# 2002A.net
KiCad netlist of a schematic drawn in Altium Designer
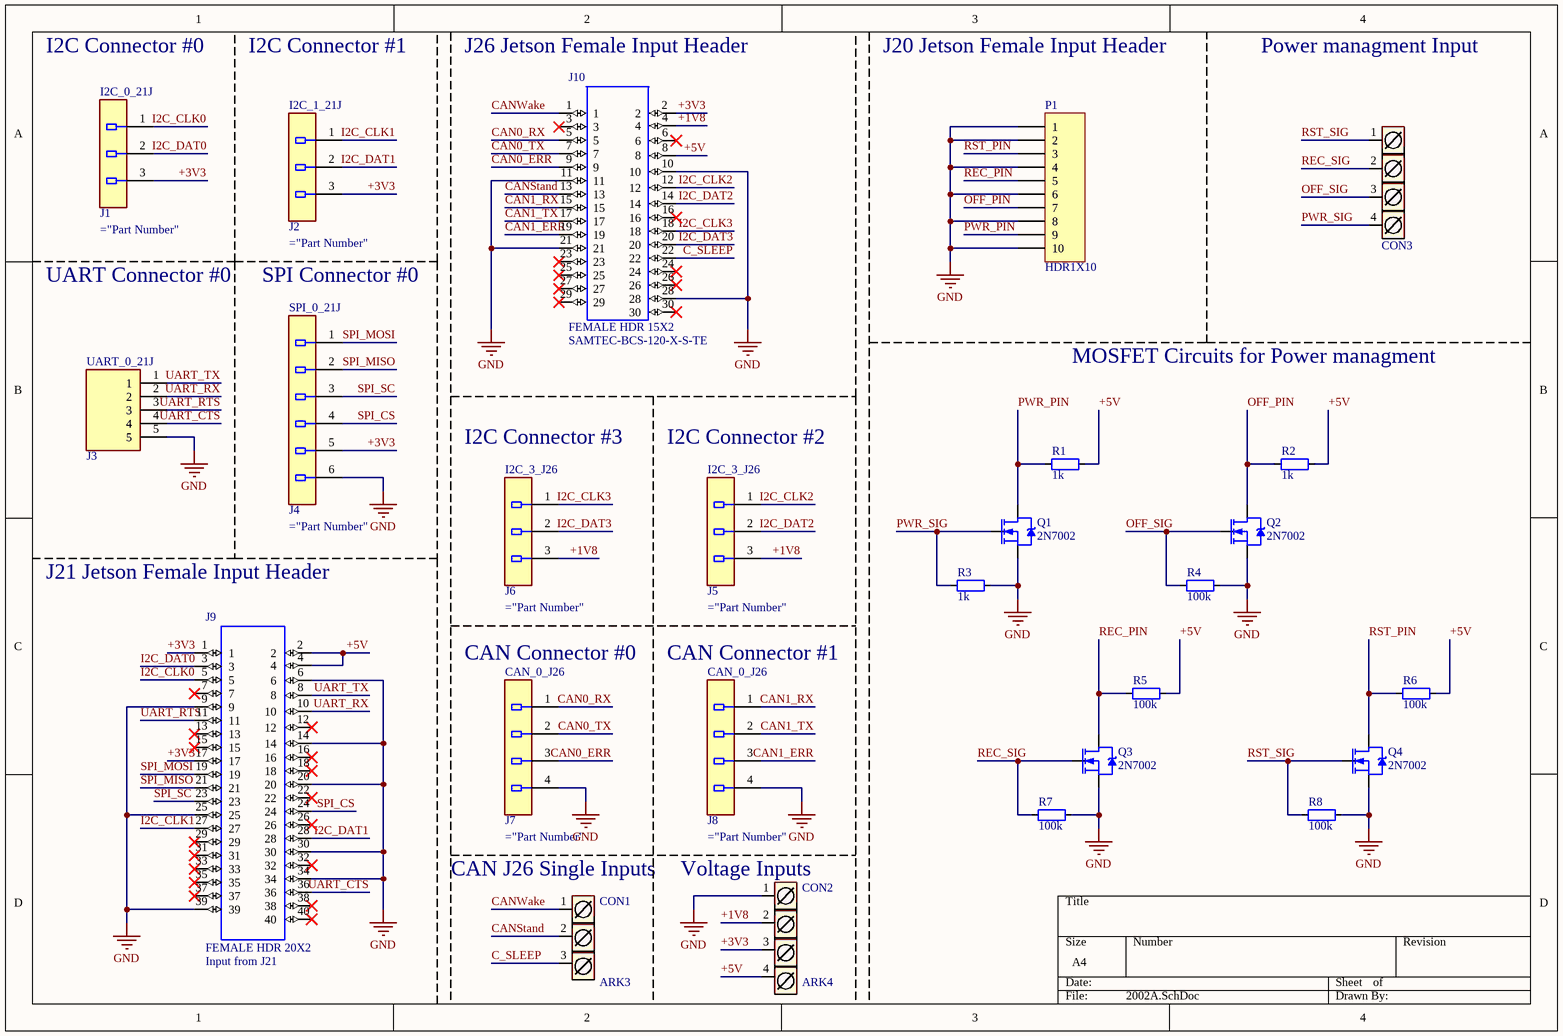
[diagram p0: 2002A.SchDoc]

(export (version "E")
  (design (tool "Eeschema 10.0.6"))
  (components
    (comp (ref "CON1")
      (value "ARK3")
      (footprint "ARK3")
      (description "Złącze śrubowe 3 piny")
      (libsource (lib "KNR_Kurs") (part "ARK3"))
    )
    (comp (ref "CON2")
      (value "ARK4")
      (footprint "ARK4")
      (description "Złącze śrubowe 4 piny")
      (libsource (lib "KNR_Kurs") (part "ARK4"))
    )
    (comp (ref "CON3")
      (value "ARK4")
      (footprint "ARK4")
      (description "Złącze śrubowe 4 piny")
      (libsource (lib "biblioteka_schematic") (part "ARK4"))
    )
    (comp (ref "J1")
      (value "I2C_0_21J")
      (footprint "Molex_22-05-7035_MFG")
      (description "I2C0")
      (libsource (lib "Conn_Molex_22-05-7035_eec") (part "22-05-7035"))
    )
    (comp (ref "J2")
      (value "I2C_1_21J")
      (footprint "Molex_22-05-7035_MFG")
      (description "I2C1")
      (libsource (lib "Conn_Molex_22-05-7035_eec") (part "22-05-7035"))
    )
    (comp (ref "J3")
      (value "UART_0_21J")
      (footprint "SamacSys:0022057055")
      (description "Connector")
      (fields (field (name "MANUFACTURER_PART_NUMBER") "0022057055"))
      (libsource (lib "MolexSpox5Ver") (part "0022057055"))
    )
    (comp (ref "J4")
      (value "SPI_0_21J")
      (footprint "Molex_22-05-7065_0")
      (libsource (lib "Conn_Molex_22-05-7065_eec") (part "22-05-7065"))
    )
    (comp (ref "J5")
      (value "I2C_3_J26")
      (footprint "Molex_22-05-7035_MFG")
      (description "I2C2")
      (libsource (lib "Conn_Molex_22-05-7035_eec") (part "22-05-7035"))
    )
    (comp (ref "J6")
      (value "I2C_3_J26")
      (footprint "Molex_22-05-7035_MFG")
      (description "I2C3")
      (libsource (lib "Conn_Molex_22-05-7035_eec") (part "22-05-7035"))
    )
    (comp (ref "J7")
      (value "CAN_0_J26")
      (footprint "Molex_22-05-7045_0")
      (description "CAN0")
      (libsource (lib "Conn_Molex_22-05-7045_eec") (part "22-05-7045"))
    )
    (comp (ref "J8")
      (value "CAN_0_J26")
      (footprint "Molex_22-05-7045_0")
      (description "CAN1")
      (libsource (lib "Conn_Molex_22-05-7045_eec") (part "22-05-7045"))
    )
    (comp (ref "J9")
      (value "Input from J21")
      (footprint "SSW-120-XX-X-D")
      (description "20 Position Receptacle Connector Through Hole")
      (fields (field (name "MP") "BCS-120-S-S-TE") (field (name "MF") "Samtec"))
      (libsource (lib "fHDR20x2") (part "SAMTEC-BCS-120-X-S-TE"))
    )
    (comp (ref "J10")
      (value "SAMTEC-BCS-120-X-S-TE")
      (footprint "SSW-115-XX-XXX-D")
      (description "20 Position Receptacle Connector Through Hole")
      (fields (field (name "MP") "BCS-120-S-S-TE") (field (name "MF") "Samtec"))
      (libsource (lib "fHDR15x2") (part "SAMTEC-BCS-120-X-S-TE"))
    )
    (comp (ref "P1")
      (value "HDR1X10")
      (footprint "biblioteka_pcb:HDR1X10")
      (description "Header, 10-Pin")
      (fields (field (name "PUBLISHER") "Altium Limited"))
      (libsource (lib "biblioteka_schematic") (part "HDR1X10"))
    )
    (comp (ref "Q1") (value "2N7002") (footprint "SOT23") (libsource (lib "KNR_Kurs") (part "2N7002")))
    (comp (ref "Q2") (value "2N7002") (footprint "SOT23") (libsource (lib "KNR_Kurs") (part "2N7002")))
    (comp (ref "Q3") (value "2N7002") (footprint "SOT23") (libsource (lib "KNR_Kurs") (part "2N7002")))
    (comp (ref "Q4") (value "2N7002") (footprint "SOT23") (libsource (lib "KNR_Kurs") (part "2N7002")))
    (comp (ref "R1")
      (value "1k")
      (footprint "0603")
      (description "Resistior")
      (libsource (lib "biblioteka_schematic") (part "RES"))
    )
    (comp (ref "R2")
      (value "1k")
      (footprint "0603")
      (description "Resistior")
      (libsource (lib "biblioteka_schematic") (part "RES"))
    )
    (comp (ref "R3")
      (value "1k")
      (footprint "0603")
      (description "Resistior")
      (libsource (lib "biblioteka_schematic") (part "RES"))
    )
    (comp (ref "R4")
      (value "100k")
      (footprint "0603")
      (description "Resistior")
      (libsource (lib "biblioteka_schematic") (part "RES"))
    )
    (comp (ref "R5")
      (value "100k")
      (footprint "0603")
      (description "Resistior")
      (libsource (lib "biblioteka_schematic") (part "RES"))
    )
    (comp (ref "R6")
      (value "100k")
      (footprint "0603")
      (description "Resistior")
      (libsource (lib "biblioteka_schematic") (part "RES"))
    )
    (comp (ref "R7")
      (value "100k")
      (footprint "0603")
      (description "Resistior")
      (libsource (lib "biblioteka_schematic") (part "RES"))
    )
    (comp (ref "R8")
      (value "100k")
      (footprint "0603")
      (description "Resistior")
      (libsource (lib "biblioteka_schematic") (part "RES"))
    )
  )
  (nets
    (net (code "1") (name "/+1V8") (class "Default")
      (node (ref "CON2") (pin "2") (pinfunction "2_2") (pintype "passive"))
      (node (ref "J10") (pin "4") (pinfunction "4_4") (pintype "bidirectional"))
      (node (ref "J5") (pin "3") (pinfunction "3_3") (pintype "passive"))
      (node (ref "J6") (pin "3") (pinfunction "3_3") (pintype "passive"))
    )
    (net (code "2") (name "/+3V3") (class "Default")
      (node (ref "CON2") (pin "3") (pinfunction "3_3") (pintype "passive"))
      (node (ref "J1") (pin "3") (pinfunction "3_3") (pintype "passive"))
      (node (ref "J10") (pin "2") (pinfunction "2_2") (pintype "bidirectional"))
      (node (ref "J2") (pin "3") (pinfunction "3_3") (pintype "passive"))
      (node (ref "J4") (pin "5") (pinfunction "5_5") (pintype "passive"))
      (node (ref "J9") (pin "1") (pinfunction "1_1") (pintype "bidirectional"))
      (node (ref "J9") (pin "17") (pinfunction "17_17") (pintype "bidirectional"))
    )
    (net (code "3") (name "/+5V") (class "Default")
      (node (ref "CON2") (pin "4") (pinfunction "4_4") (pintype "passive"))
      (node (ref "J10") (pin "8") (pinfunction "8_8") (pintype "bidirectional"))
      (node (ref "J9") (pin "2") (pinfunction "2_2") (pintype "bidirectional"))
      (node (ref "J9") (pin "4") (pinfunction "4_4") (pintype "bidirectional"))
      (node (ref "R1") (pin "2") (pinfunction "2_2") (pintype "passive"))
      (node (ref "R2") (pin "2") (pinfunction "2_2") (pintype "passive"))
      (node (ref "R5") (pin "2") (pinfunction "2_2") (pintype "passive"))
      (node (ref "R6") (pin "2") (pinfunction "2_2") (pintype "passive"))
    )
    (net (code "4") (name "/CAN0_ERR") (class "Default")
      (node (ref "J10") (pin "9") (pinfunction "9_9") (pintype "bidirectional"))
      (node (ref "J7") (pin "3") (pinfunction "3_3") (pintype "passive"))
    )
    (net (code "5") (name "/CAN0_RX") (class "Default")
      (node (ref "J10") (pin "5") (pinfunction "5_5") (pintype "bidirectional"))
      (node (ref "J7") (pin "1") (pinfunction "1_1") (pintype "passive"))
    )
    (net (code "6") (name "/CAN0_TX") (class "Default")
      (node (ref "J10") (pin "7") (pinfunction "7_7") (pintype "bidirectional"))
      (node (ref "J7") (pin "2") (pinfunction "2_2") (pintype "passive"))
    )
    (net (code "7") (name "/CAN1_ERR") (class "Default")
      (node (ref "J10") (pin "19") (pinfunction "19_19") (pintype "bidirectional"))
      (node (ref "J8") (pin "3") (pinfunction "3_3") (pintype "passive"))
    )
    (net (code "8") (name "/CAN1_RX") (class "Default")
      (node (ref "J10") (pin "15") (pinfunction "15_15") (pintype "bidirectional"))
      (node (ref "J8") (pin "1") (pinfunction "1_1") (pintype "passive"))
    )
    (net (code "9") (name "/CAN1_TX") (class "Default")
      (node (ref "J10") (pin "17") (pinfunction "17_17") (pintype "bidirectional"))
      (node (ref "J8") (pin "2") (pinfunction "2_2") (pintype "passive"))
    )
    (net (code "10") (name "/CANStand") (class "Default")
      (node (ref "CON1") (pin "2") (pinfunction "2_2") (pintype "passive"))
      (node (ref "J10") (pin "13") (pinfunction "13_13") (pintype "bidirectional"))
    )
    (net (code "11") (name "/CANWake") (class "Default")
      (node (ref "CON1") (pin "1") (pinfunction "1_1") (pintype "passive"))
      (node (ref "J10") (pin "1") (pinfunction "1_1") (pintype "bidirectional"))
    )
    (net (code "12") (name "/C_SLEEP") (class "Default")
      (node (ref "CON1") (pin "3") (pinfunction "3_3") (pintype "passive"))
      (node (ref "J10") (pin "22") (pinfunction "22_22") (pintype "bidirectional"))
    )
    (net (code "13") (name "/I2C_CLK0") (class "Default")
      (node (ref "J1") (pin "1") (pinfunction "1_1") (pintype "passive"))
      (node (ref "J9") (pin "5") (pinfunction "5_5") (pintype "bidirectional"))
    )
    (net (code "14") (name "/I2C_CLK1") (class "Default")
      (node (ref "J2") (pin "1") (pinfunction "1_1") (pintype "passive"))
      (node (ref "J9") (pin "27") (pinfunction "27_27") (pintype "bidirectional"))
    )
    (net (code "15") (name "/I2C_CLK2") (class "Default")
      (node (ref "J10") (pin "12") (pinfunction "12_12") (pintype "bidirectional"))
      (node (ref "J5") (pin "1") (pinfunction "1_1") (pintype "passive"))
    )
    (net (code "16") (name "/I2C_CLK3") (class "Default")
      (node (ref "J10") (pin "18") (pinfunction "18_18") (pintype "bidirectional"))
      (node (ref "J6") (pin "1") (pinfunction "1_1") (pintype "passive"))
    )
    (net (code "17") (name "/I2C_DAT0") (class "Default")
      (node (ref "J1") (pin "2") (pinfunction "2_2") (pintype "passive"))
      (node (ref "J9") (pin "3") (pinfunction "3_3") (pintype "bidirectional"))
    )
    (net (code "18") (name "/I2C_DAT1") (class "Default")
      (node (ref "J2") (pin "2") (pinfunction "2_2") (pintype "passive"))
      (node (ref "J9") (pin "28") (pinfunction "28_28") (pintype "bidirectional"))
    )
    (net (code "19") (name "/I2C_DAT2") (class "Default")
      (node (ref "J10") (pin "14") (pinfunction "14_14") (pintype "bidirectional"))
      (node (ref "J5") (pin "2") (pinfunction "2_2") (pintype "passive"))
    )
    (net (code "20") (name "/I2C_DAT3") (class "Default")
      (node (ref "J10") (pin "20") (pinfunction "20_20") (pintype "bidirectional"))
      (node (ref "J6") (pin "2") (pinfunction "2_2") (pintype "passive"))
    )
    (net (code "21") (name "/OFF_PIN") (class "Default")
      (node (ref "P1") (pin "7") (pinfunction "7_7") (pintype "passive"))
      (node (ref "Q2") (pin "3") (pinfunction "D_3") (pintype "passive"))
      (node (ref "R2") (pin "1") (pinfunction "1_1") (pintype "passive"))
    )
    (net (code "22") (name "/OFF_SIG") (class "Default")
      (node (ref "CON3") (pin "3") (pinfunction "3_3") (pintype "passive"))
      (node (ref "Q2") (pin "1") (pinfunction "G_1") (pintype "passive"))
      (node (ref "R4") (pin "1") (pinfunction "1_1") (pintype "passive"))
    )
    (net (code "23") (name "/PWR_PIN") (class "Default")
      (node (ref "P1") (pin "9") (pinfunction "9_9") (pintype "passive"))
      (node (ref "Q1") (pin "3") (pinfunction "D_3") (pintype "passive"))
      (node (ref "R1") (pin "1") (pinfunction "1_1") (pintype "passive"))
    )
    (net (code "24") (name "/PWR_SIG") (class "Default")
      (node (ref "CON3") (pin "4") (pinfunction "4_4") (pintype "passive"))
      (node (ref "Q1") (pin "1") (pinfunction "G_1") (pintype "passive"))
      (node (ref "R3") (pin "1") (pinfunction "1_1") (pintype "passive"))
    )
    (net (code "25") (name "/REC_PIN") (class "Default")
      (node (ref "P1") (pin "5") (pinfunction "5_5") (pintype "passive"))
      (node (ref "Q3") (pin "3") (pinfunction "D_3") (pintype "passive"))
      (node (ref "R5") (pin "1") (pinfunction "1_1") (pintype "passive"))
    )
    (net (code "26") (name "/REC_SIG") (class "Default")
      (node (ref "CON3") (pin "2") (pinfunction "2_2") (pintype "passive"))
      (node (ref "Q3") (pin "1") (pinfunction "G_1") (pintype "passive"))
      (node (ref "R7") (pin "1") (pinfunction "1_1") (pintype "passive"))
    )
    (net (code "27") (name "/RST_PIN") (class "Default")
      (node (ref "P1") (pin "3") (pinfunction "3_3") (pintype "passive"))
      (node (ref "Q4") (pin "3") (pinfunction "D_3") (pintype "passive"))
      (node (ref "R6") (pin "1") (pinfunction "1_1") (pintype "passive"))
    )
    (net (code "28") (name "/RST_SIG") (class "Default")
      (node (ref "CON3") (pin "1") (pinfunction "1_1") (pintype "passive"))
      (node (ref "Q4") (pin "1") (pinfunction "G_1") (pintype "passive"))
      (node (ref "R8") (pin "1") (pinfunction "1_1") (pintype "passive"))
    )
    (net (code "29") (name "/SPI_CS") (class "Default")
      (node (ref "J4") (pin "4") (pinfunction "4_4") (pintype "passive"))
      (node (ref "J9") (pin "24") (pinfunction "24_24") (pintype "bidirectional"))
    )
    (net (code "30") (name "/SPI_MISO") (class "Default")
      (node (ref "J4") (pin "2") (pinfunction "2_2") (pintype "passive"))
      (node (ref "J9") (pin "21") (pinfunction "21_21") (pintype "bidirectional"))
    )
    (net (code "31") (name "/SPI_MOSI") (class "Default")
      (node (ref "J4") (pin "1") (pinfunction "1_1") (pintype "passive"))
      (node (ref "J9") (pin "19") (pinfunction "19_19") (pintype "bidirectional"))
    )
    (net (code "32") (name "/SPI_SC") (class "Default")
      (node (ref "J4") (pin "3") (pinfunction "3_3") (pintype "passive"))
      (node (ref "J9") (pin "23") (pinfunction "23_23") (pintype "bidirectional"))
    )
    (net (code "33") (name "/UART_CTS") (class "Default")
      (node (ref "J3") (pin "4") (pinfunction "4_4") (pintype "passive"))
      (node (ref "J9") (pin "36") (pinfunction "36_36") (pintype "bidirectional"))
    )
    (net (code "34") (name "/UART_RTS") (class "Default")
      (node (ref "J3") (pin "3") (pinfunction "3_3") (pintype "passive"))
      (node (ref "J9") (pin "11") (pinfunction "11_11") (pintype "bidirectional"))
    )
    (net (code "35") (name "/UART_RX") (class "Default")
      (node (ref "J3") (pin "2") (pinfunction "2_2") (pintype "passive"))
      (node (ref "J9") (pin "10") (pinfunction "10_10") (pintype "bidirectional"))
    )
    (net (code "36") (name "/UART_TX") (class "Default")
      (node (ref "J3") (pin "1") (pinfunction "1_1") (pintype "passive"))
      (node (ref "J9") (pin "8") (pinfunction "8_8") (pintype "bidirectional"))
    )
    (net (code "37") (name "GND") (class "Default")
      (node (ref "CON2") (pin "1") (pinfunction "1_1") (pintype "passive"))
      (node (ref "J10") (pin "10") (pinfunction "10_10") (pintype "bidirectional"))
      (node (ref "J10") (pin "11") (pinfunction "11_11") (pintype "bidirectional"))
      (node (ref "J10") (pin "21") (pinfunction "21_21") (pintype "bidirectional"))
      (node (ref "J10") (pin "28") (pinfunction "28_28") (pintype "bidirectional"))
      (node (ref "J3") (pin "5") (pinfunction "5_5") (pintype "passive"))
      (node (ref "J4") (pin "6") (pinfunction "6_6") (pintype "passive"))
      (node (ref "J7") (pin "4") (pinfunction "4_4") (pintype "passive"))
      (node (ref "J8") (pin "4") (pinfunction "4_4") (pintype "passive"))
      (node (ref "J9") (pin "14") (pinfunction "14_14") (pintype "bidirectional"))
      (node (ref "J9") (pin "20") (pinfunction "20_20") (pintype "bidirectional"))
      (node (ref "J9") (pin "25") (pinfunction "25_25") (pintype "bidirectional"))
      (node (ref "J9") (pin "30") (pinfunction "30_30") (pintype "bidirectional"))
      (node (ref "J9") (pin "34") (pinfunction "34_34") (pintype "bidirectional"))
      (node (ref "J9") (pin "39") (pinfunction "39_39") (pintype "bidirectional"))
      (node (ref "J9") (pin "6") (pinfunction "6_6") (pintype "bidirectional"))
      (node (ref "J9") (pin "9") (pinfunction "9_9") (pintype "bidirectional"))
      (node (ref "P1") (pin "1") (pinfunction "1_1") (pintype "passive"))
      (node (ref "P1") (pin "10") (pinfunction "10_10") (pintype "passive"))
      (node (ref "P1") (pin "2") (pinfunction "2_2") (pintype "passive"))
      (node (ref "P1") (pin "4") (pinfunction "4_4") (pintype "passive"))
      (node (ref "P1") (pin "6") (pinfunction "6_6") (pintype "passive"))
      (node (ref "P1") (pin "8") (pinfunction "8_8") (pintype "passive"))
      (node (ref "Q1") (pin "2") (pinfunction "S_2") (pintype "passive"))
      (node (ref "Q2") (pin "2") (pinfunction "S_2") (pintype "passive"))
      (node (ref "Q3") (pin "2") (pinfunction "S_2") (pintype "passive"))
      (node (ref "Q4") (pin "2") (pinfunction "S_2") (pintype "passive"))
      (node (ref "R3") (pin "2") (pinfunction "2_2") (pintype "passive"))
      (node (ref "R4") (pin "2") (pinfunction "2_2") (pintype "passive"))
      (node (ref "R7") (pin "2") (pinfunction "2_2") (pintype "passive"))
      (node (ref "R8") (pin "2") (pinfunction "2_2") (pintype "passive"))
    )
    (net (code "38") (name "unconnected-(J9-Pad7)") (class "Default")
      (node (ref "J9") (pin "7") (pinfunction "7_7") (pintype "bidirectional+no_connect"))
    )
    (net (code "39") (name "unconnected-(J9-Pad12)") (class "Default")
      (node (ref "J9") (pin "12") (pinfunction "12_12") (pintype "bidirectional+no_connect"))
    )
    (net (code "40") (name "unconnected-(J9-Pad13)") (class "Default")
      (node (ref "J9") (pin "13") (pinfunction "13_13") (pintype "bidirectional+no_connect"))
    )
    (net (code "41") (name "unconnected-(J9-Pad15)") (class "Default")
      (node (ref "J9") (pin "15") (pinfunction "15_15") (pintype "bidirectional+no_connect"))
    )
    (net (code "42") (name "unconnected-(J9-Pad16)") (class "Default")
      (node (ref "J9") (pin "16") (pinfunction "16_16") (pintype "bidirectional+no_connect"))
    )
    (net (code "43") (name "unconnected-(J9-Pad18)") (class "Default")
      (node (ref "J9") (pin "18") (pinfunction "18_18") (pintype "bidirectional+no_connect"))
    )
    (net (code "44") (name "unconnected-(J9-Pad22)") (class "Default")
      (node (ref "J9") (pin "22") (pinfunction "22_22") (pintype "bidirectional+no_connect"))
    )
    (net (code "45") (name "unconnected-(J9-Pad26)") (class "Default")
      (node (ref "J9") (pin "26") (pinfunction "26_26") (pintype "bidirectional+no_connect"))
    )
    (net (code "46") (name "unconnected-(J9-Pad29)") (class "Default")
      (node (ref "J9") (pin "29") (pinfunction "29_29") (pintype "bidirectional+no_connect"))
    )
    (net (code "47") (name "unconnected-(J9-Pad31)") (class "Default")
      (node (ref "J9") (pin "31") (pinfunction "31_31") (pintype "bidirectional+no_connect"))
    )
    (net (code "48") (name "unconnected-(J9-Pad32)") (class "Default")
      (node (ref "J9") (pin "32") (pinfunction "32_32") (pintype "bidirectional+no_connect"))
    )
    (net (code "49") (name "unconnected-(J9-Pad33)") (class "Default")
      (node (ref "J9") (pin "33") (pinfunction "33_33") (pintype "bidirectional+no_connect"))
    )
    (net (code "50") (name "unconnected-(J9-Pad35)") (class "Default")
      (node (ref "J9") (pin "35") (pinfunction "35_35") (pintype "bidirectional+no_connect"))
    )
    (net (code "51") (name "unconnected-(J9-Pad37)") (class "Default")
      (node (ref "J9") (pin "37") (pinfunction "37_37") (pintype "bidirectional+no_connect"))
    )
    (net (code "52") (name "unconnected-(J9-Pad38)") (class "Default")
      (node (ref "J9") (pin "38") (pinfunction "38_38") (pintype "bidirectional+no_connect"))
    )
    (net (code "53") (name "unconnected-(J9-Pad40)") (class "Default")
      (node (ref "J9") (pin "40") (pinfunction "40_40") (pintype "bidirectional+no_connect"))
    )
    (net (code "54") (name "unconnected-(J10-Pad3)") (class "Default")
      (node (ref "J10") (pin "3") (pinfunction "3_3") (pintype "bidirectional+no_connect"))
    )
    (net (code "55") (name "unconnected-(J10-Pad6)") (class "Default")
      (node (ref "J10") (pin "6") (pinfunction "6_6") (pintype "bidirectional+no_connect"))
    )
    (net (code "56") (name "unconnected-(J10-Pad16)") (class "Default")
      (node (ref "J10") (pin "16") (pinfunction "16_16") (pintype "bidirectional+no_connect"))
    )
    (net (code "57") (name "unconnected-(J10-Pad23)") (class "Default")
      (node (ref "J10") (pin "23") (pinfunction "23_23") (pintype "bidirectional+no_connect"))
    )
    (net (code "58") (name "unconnected-(J10-Pad24)") (class "Default")
      (node (ref "J10") (pin "24") (pinfunction "24_24") (pintype "bidirectional+no_connect"))
    )
    (net (code "59") (name "unconnected-(J10-Pad25)") (class "Default")
      (node (ref "J10") (pin "25") (pinfunction "25_25") (pintype "bidirectional+no_connect"))
    )
    (net (code "60") (name "unconnected-(J10-Pad26)") (class "Default")
      (node (ref "J10") (pin "26") (pinfunction "26_26") (pintype "bidirectional+no_connect"))
    )
    (net (code "61") (name "unconnected-(J10-Pad27)") (class "Default")
      (node (ref "J10") (pin "27") (pinfunction "27_27") (pintype "bidirectional+no_connect"))
    )
    (net (code "62") (name "unconnected-(J10-Pad29)") (class "Default")
      (node (ref "J10") (pin "29") (pinfunction "29_29") (pintype "bidirectional+no_connect"))
    )
    (net (code "63") (name "unconnected-(J10-Pad30)") (class "Default")
      (node (ref "J10") (pin "30") (pinfunction "30_30") (pintype "bidirectional+no_connect"))
    )
  )
)
